# LatarTouch.net
KiCad netlist of a schematic drawn in EAGLE
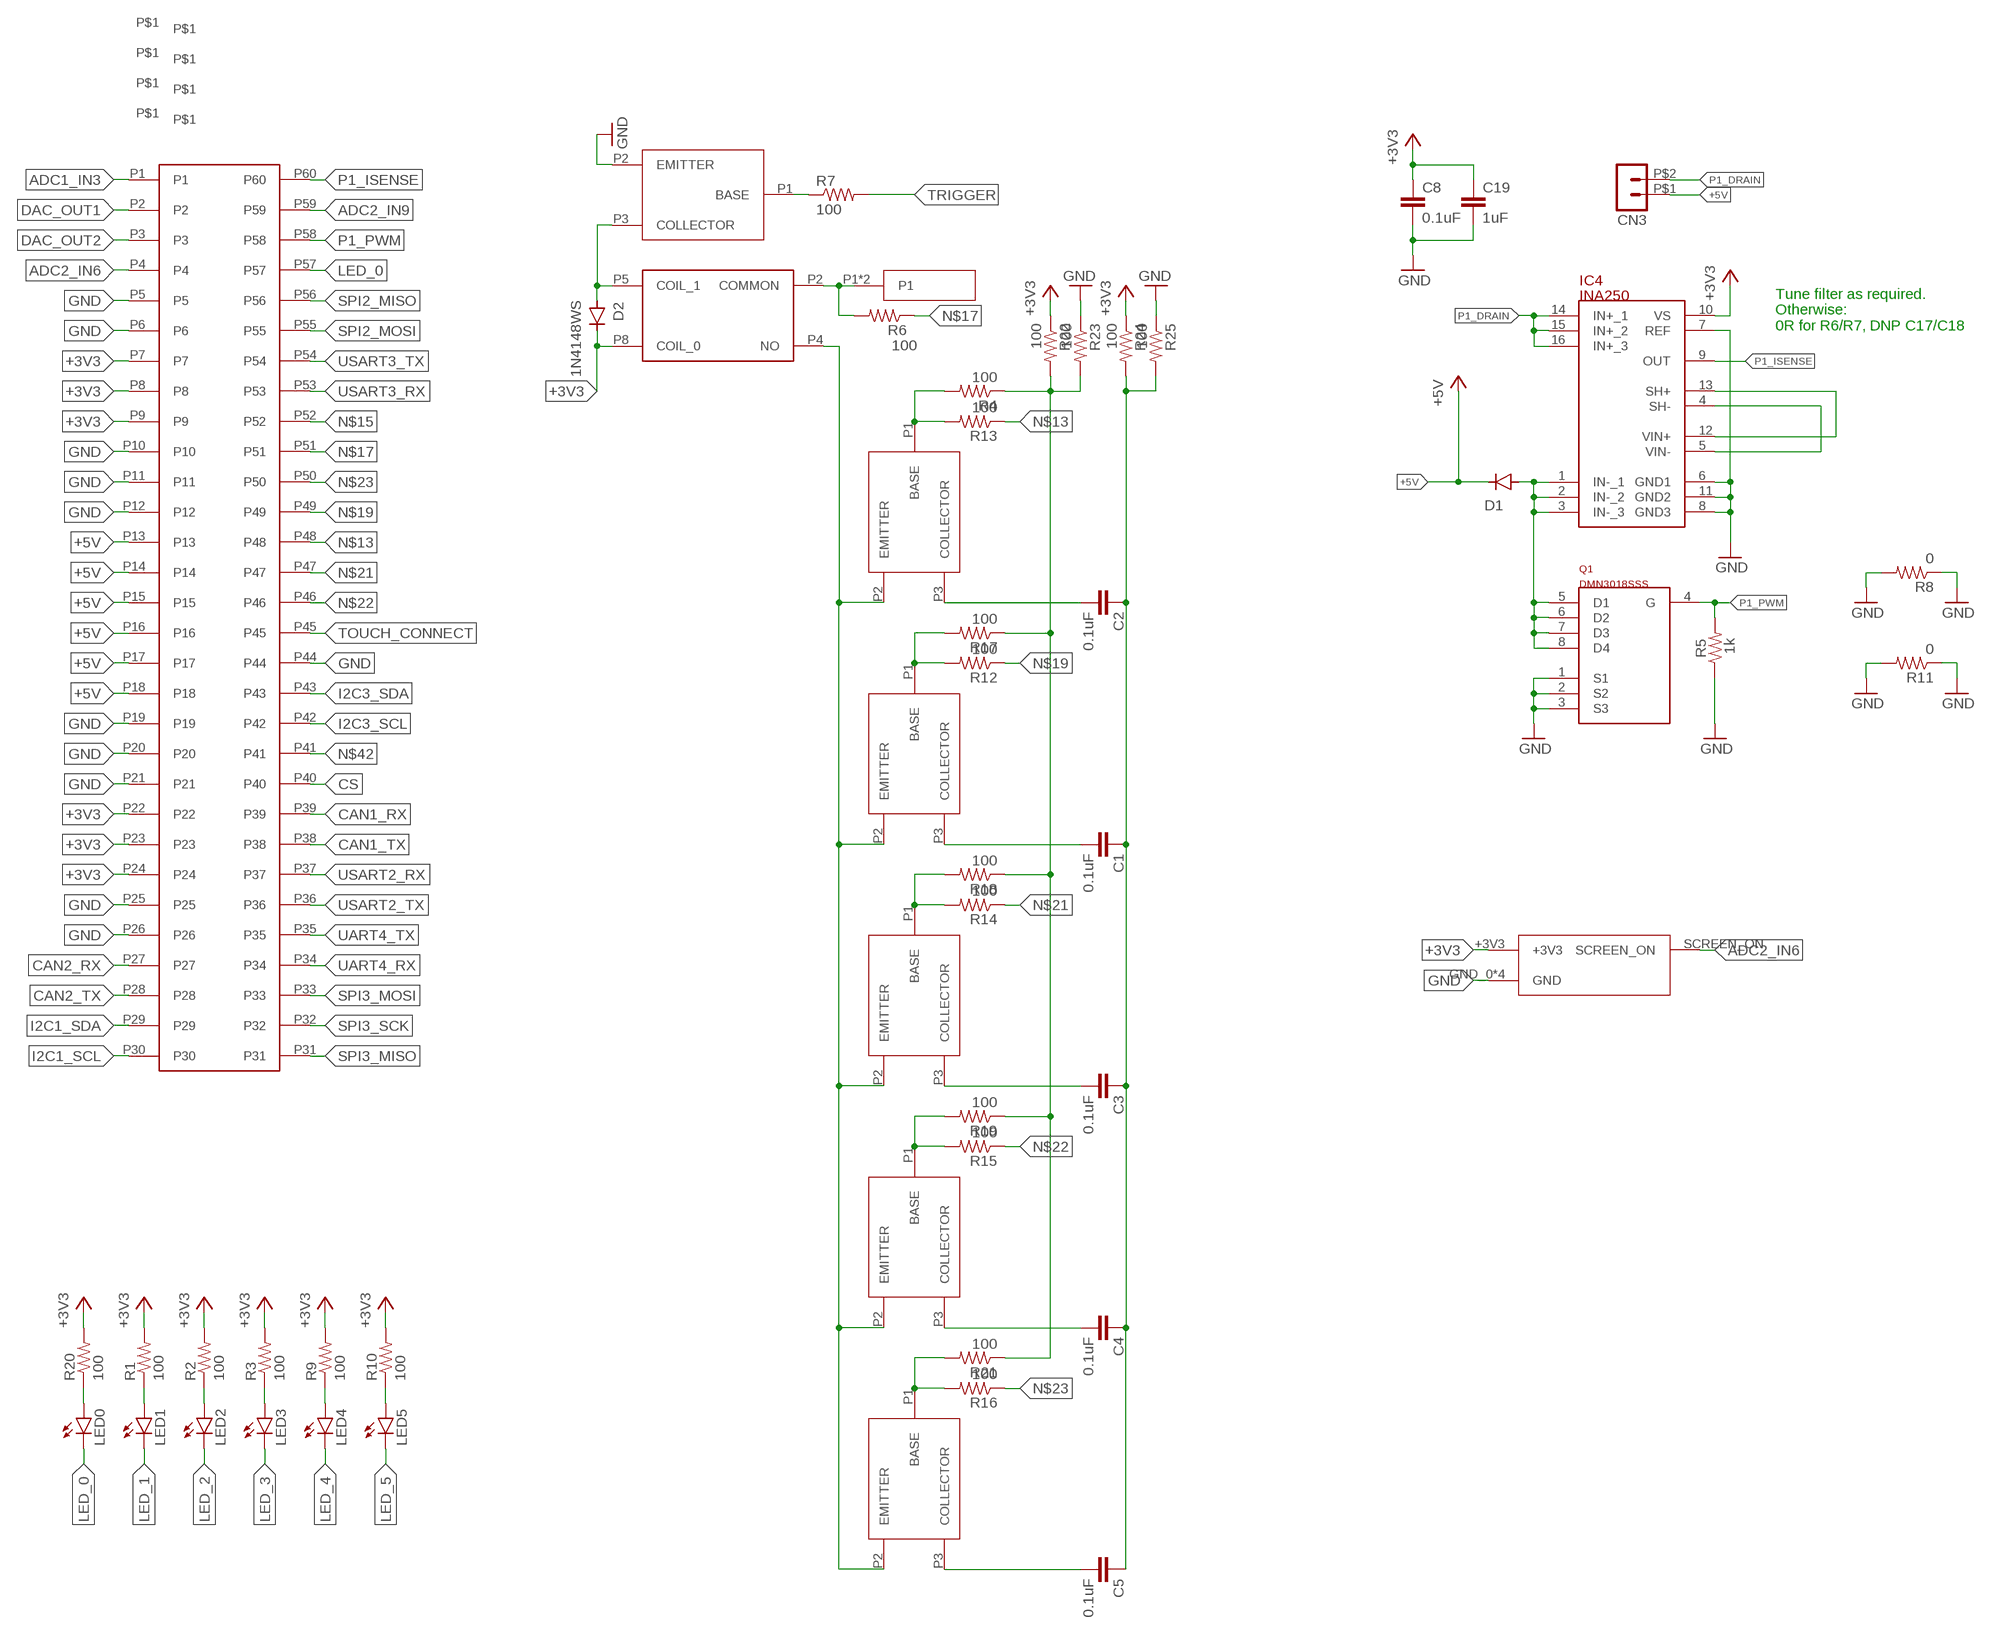
[diagram p0: schematic, sheet 1]

(export (version "E")
  (design (tool "Eeschema 10.0.6"))
  (components
    (comp (ref "C1")
      (value "0.1uF")
      (footprint "eagle-import:C0603")
      (libsource (lib "eagle-import") (part "C-EUC0603"))
    )
    (comp (ref "C2")
      (value "0.1uF")
      (footprint "eagle-import:C0603")
      (libsource (lib "eagle-import") (part "C-EUC0603"))
    )
    (comp (ref "C3")
      (value "0.1uF")
      (footprint "eagle-import:C0603")
      (libsource (lib "eagle-import") (part "C-EUC0603"))
    )
    (comp (ref "C4")
      (value "0.1uF")
      (footprint "eagle-import:C0603")
      (libsource (lib "eagle-import") (part "C-EUC0603"))
    )
    (comp (ref "C5")
      (value "0.1uF")
      (footprint "eagle-import:C0603")
      (libsource (lib "eagle-import") (part "C-EUC0603"))
    )
    (comp (ref "C8")
      (value "0.1uF")
      (footprint "eagle-import:C0805")
      (libsource (lib "eagle-import") (part "C-EUC0805"))
    )
    (comp (ref "C19")
      (value "1uF")
      (footprint "eagle-import:C0805")
      (libsource (lib "eagle-import") (part "C-EUC0805"))
    )
    (comp (ref "CN3")
      (value "HEADER_POS2_43650-0212")
      (footprint "eagle-import:43650-0212")
      (libsource (lib "eagle-import") (part "HEADER_POS2_?43650-0212"))
    )
    (comp (ref "D1")
      (value "DIODE-DO214AC")
      (footprint "eagle-import:DO214AC")
      (libsource (lib "eagle-import") (part "DIODE-DO214AC"))
    )
    (comp (ref "D2")
      (value "1N4148WS")
      (footprint "eagle-import:SOD-323")
      (fields
        (field (name "DIGIKEY_PART_NUMBER") "1N4148WSFSTR-ND")
        (field (name "MANUFACTURER") "Diodes Incorporated")
        (field (name "CREATED_BY") "PCBLayout.com")
      )
      (libsource (lib "eagle-import") (part "1N4148WS"))
    )
    (comp (ref "IC4")
      (value "INA250")
      (footprint "eagle-import:TSSOP16")
      (libsource (lib "eagle-import") (part "INA250"))
    )
    (comp (ref "LED0")
      (value "LEDCHIPLED_0603")
      (footprint "eagle-import:CHIPLED_0603")
      (libsource (lib "eagle-import") (part "LEDCHIPLED_0603"))
    )
    (comp (ref "LED1")
      (value "LEDCHIPLED_0603")
      (footprint "eagle-import:CHIPLED_0603")
      (libsource (lib "eagle-import") (part "LEDCHIPLED_0603"))
    )
    (comp (ref "LED2")
      (value "LEDCHIPLED_0603")
      (footprint "eagle-import:CHIPLED_0603")
      (libsource (lib "eagle-import") (part "LEDCHIPLED_0603"))
    )
    (comp (ref "LED3")
      (value "LEDCHIPLED_0603")
      (footprint "eagle-import:CHIPLED_0603")
      (libsource (lib "eagle-import") (part "LEDCHIPLED_0603"))
    )
    (comp (ref "LED4")
      (value "LEDCHIPLED_0603")
      (footprint "eagle-import:CHIPLED_0603")
      (libsource (lib "eagle-import") (part "LEDCHIPLED_0603"))
    )
    (comp (ref "LED5")
      (value "LEDCHIPLED_0603")
      (footprint "eagle-import:CHIPLED_0603")
      (libsource (lib "eagle-import") (part "LEDCHIPLED_0603"))
    )
    (comp (ref "Q1")
      (value "DMN3018SSS")
      (footprint "eagle-import:SO08")
      (libsource (lib "eagle-import") (part "DMN3018SSS"))
    )
    (comp (ref "R1")
      (value "100")
      (footprint "eagle-import:R0603")
      (libsource (lib "eagle-import") (part "R-US_R0603"))
    )
    (comp (ref "R2")
      (value "100")
      (footprint "eagle-import:R0603")
      (libsource (lib "eagle-import") (part "R-US_R0603"))
    )
    (comp (ref "R3")
      (value "100")
      (footprint "eagle-import:R0603")
      (libsource (lib "eagle-import") (part "R-US_R0603"))
    )
    (comp (ref "R4")
      (value "100")
      (footprint "eagle-import:R0603")
      (libsource (lib "eagle-import") (part "resistor_348_R-US_R0603"))
    )
    (comp (ref "R5")
      (value "1k")
      (footprint "eagle-import:0805")
      (libsource (lib "eagle-import") (part "RESISTOR0805"))
    )
    (comp (ref "R6")
      (value "100")
      (footprint "eagle-import:R0603")
      (libsource (lib "eagle-import") (part "R-US_R0603"))
    )
    (comp (ref "R7")
      (value "100")
      (footprint "eagle-import:R0603")
      (libsource (lib "eagle-import") (part "R-US_R0603"))
    )
    (comp (ref "R8")
      (value "0")
      (footprint "eagle-import:R0603")
      (libsource (lib "eagle-import") (part "R-US_R0603"))
    )
    (comp (ref "R9")
      (value "100")
      (footprint "eagle-import:R0603")
      (libsource (lib "eagle-import") (part "R-US_R0603"))
    )
    (comp (ref "R10")
      (value "100")
      (footprint "eagle-import:R0603")
      (libsource (lib "eagle-import") (part "R-US_R0603"))
    )
    (comp (ref "R11")
      (value "0")
      (footprint "eagle-import:R1206")
      (libsource (lib "eagle-import") (part "resistor_348_R-US_R1206"))
    )
    (comp (ref "R12")
      (value "100")
      (footprint "eagle-import:R0603")
      (libsource (lib "eagle-import") (part "resistor_348_R-US_R0603"))
    )
    (comp (ref "R13")
      (value "100")
      (footprint "eagle-import:R0603")
      (libsource (lib "eagle-import") (part "resistor_348_R-US_R0603"))
    )
    (comp (ref "R14")
      (value "100")
      (footprint "eagle-import:R0603")
      (libsource (lib "eagle-import") (part "resistor_348_R-US_R0603"))
    )
    (comp (ref "R15")
      (value "100")
      (footprint "eagle-import:R0603")
      (libsource (lib "eagle-import") (part "resistor_348_R-US_R0603"))
    )
    (comp (ref "R16")
      (value "100")
      (footprint "eagle-import:R0603")
      (libsource (lib "eagle-import") (part "resistor_348_R-US_R0603"))
    )
    (comp (ref "R17")
      (value "100")
      (footprint "eagle-import:R0603")
      (libsource (lib "eagle-import") (part "resistor_348_R-US_R0603"))
    )
    (comp (ref "R18")
      (value "100")
      (footprint "eagle-import:R0603")
      (libsource (lib "eagle-import") (part "resistor_348_R-US_R0603"))
    )
    (comp (ref "R19")
      (value "100")
      (footprint "eagle-import:R0603")
      (libsource (lib "eagle-import") (part "resistor_348_R-US_R0603"))
    )
    (comp (ref "R20")
      (value "100")
      (footprint "eagle-import:R0603")
      (libsource (lib "eagle-import") (part "R-US_R0603"))
    )
    (comp (ref "R21")
      (value "100")
      (footprint "eagle-import:R0603")
      (libsource (lib "eagle-import") (part "resistor_348_R-US_R0603"))
    )
    (comp (ref "R22")
      (value "100")
      (footprint "eagle-import:R0603")
      (libsource (lib "eagle-import") (part "resistor_348_R-US_R0603"))
    )
    (comp (ref "R23")
      (value "100")
      (footprint "eagle-import:R0603")
      (libsource (lib "eagle-import") (part "resistor_348_R-US_R0603"))
    )
    (comp (ref "R24")
      (value "100")
      (footprint "eagle-import:R0603")
      (libsource (lib "eagle-import") (part "resistor_348_R-US_R0603"))
    )
    (comp (ref "R25")
      (value "100")
      (footprint "eagle-import:R0603")
      (libsource (lib "eagle-import") (part "resistor_348_R-US_R0603"))
    )
    (comp (ref "U$4")
      (value "TOUCH")
      (footprint "eagle-import:TOUCH_PROBE")
      (libsource (lib "eagle-import") (part "TOUCH_PROBE"))
    )
    (comp (ref "U$5")
      (value "MMBT3904")
      (footprint "eagle-import:SOT23")
      (libsource (lib "eagle-import") (part "MMBT3904"))
    )
    (comp (ref "U$6")
      (value "DF12(3.0)-60DS-0.5V(86)")
      (footprint "eagle-import:DF12(3.0)-60DS-0.5V(86)")
      (libsource (lib "eagle-import") (part "DF12(3.0)-60DS-0.5V(86)"))
    )
    (comp (ref "U$7")
      (value "9774030360R")
      (footprint "eagle-import:9774030360R")
      (libsource (lib "eagle-import") (part "9774030360R"))
    )
    (comp (ref "U$8")
      (value "DETECT_DAUGHTER_BOARD")
      (footprint "eagle-import:DETECT_DAUGHTER_BOARD")
      (libsource (lib "eagle-import") (part "DETECT_DAUGHTER_BOARD"))
    )
    (comp (ref "U$9")
      (value "9774030360R")
      (footprint "eagle-import:9774030360R")
      (libsource (lib "eagle-import") (part "9774030360R"))
    )
    (comp (ref "U$10")
      (value "9774030360R")
      (footprint "eagle-import:9774030360R")
      (libsource (lib "eagle-import") (part "9774030360R"))
    )
    (comp (ref "U$11")
      (value "9774030360R")
      (footprint "eagle-import:9774030360R")
      (libsource (lib "eagle-import") (part "9774030360R"))
    )
    (comp (ref "U$14")
      (value "G6L-1F")
      (footprint "eagle-import:G6L-1F")
      (libsource (lib "eagle-import") (part "G6L-1F"))
    )
    (comp (ref "U$15")
      (value "MMBT3904")
      (footprint "eagle-import:SOT23")
      (libsource (lib "eagle-import") (part "MMBT3904"))
    )
    (comp (ref "U$16")
      (value "MMBT3904")
      (footprint "eagle-import:SOT23")
      (libsource (lib "eagle-import") (part "MMBT3904"))
    )
    (comp (ref "U$17")
      (value "MMBT3904")
      (footprint "eagle-import:SOT23")
      (libsource (lib "eagle-import") (part "MMBT3904"))
    )
    (comp (ref "U$18")
      (value "MMBT3904")
      (footprint "eagle-import:SOT23")
      (libsource (lib "eagle-import") (part "MMBT3904"))
    )
    (comp (ref "U$19")
      (value "MMBT3904")
      (footprint "eagle-import:SOT23")
      (libsource (lib "eagle-import") (part "MMBT3904"))
    )
  )
  (nets
    (net (code "1") (name "+3V3") (class "Default")
      (node (ref "C19") (pin "1") (pinfunction "1_1") (pintype "passive"))
      (node (ref "C8") (pin "1") (pinfunction "1_1") (pintype "passive"))
      (node (ref "IC4") (pin "10") (pinfunction "VS_10") (pintype "bidirectional"))
      (node (ref "R1") (pin "2") (pinfunction "2_2") (pintype "passive"))
      (node (ref "R10") (pin "2") (pinfunction "2_2") (pintype "passive"))
      (node (ref "R2") (pin "2") (pinfunction "2_2") (pintype "passive"))
      (node (ref "R20") (pin "2") (pinfunction "2_2") (pintype "passive"))
      (node (ref "R22") (pin "1") (pinfunction "1_1") (pintype "passive"))
      (node (ref "R24") (pin "1") (pinfunction "1_1") (pintype "passive"))
      (node (ref "R3") (pin "2") (pinfunction "2_2") (pintype "passive"))
      (node (ref "R9") (pin "2") (pinfunction "2_2") (pintype "passive"))
      (node (ref "U$6") (pin "P22") (pinfunction "P22_P22") (pintype "bidirectional"))
      (node (ref "U$6") (pin "P23") (pinfunction "P23_P23") (pintype "bidirectional"))
      (node (ref "U$6") (pin "P24") (pinfunction "P24_P24") (pintype "bidirectional"))
      (node (ref "U$6") (pin "P7") (pinfunction "P7_P7") (pintype "bidirectional"))
      (node (ref "U$6") (pin "P8") (pinfunction "P8_P8") (pintype "bidirectional"))
      (node (ref "U$6") (pin "P9") (pinfunction "P9_P9") (pintype "bidirectional"))
      (node (ref "U$8") (pin "+3V3") (pinfunction "+3V3_+3V3") (pintype "bidirectional"))
    )
    (net (code "2") (name "+5V") (class "Default")
      (node (ref "CN3") (pin "P$1") (pinfunction "1_P$1") (pintype "passive"))
      (node (ref "D1") (pin "C") (pinfunction "C_C") (pintype "passive"))
      (node (ref "U$6") (pin "P13") (pinfunction "P13_P13") (pintype "bidirectional"))
      (node (ref "U$6") (pin "P14") (pinfunction "P14_P14") (pintype "bidirectional"))
      (node (ref "U$6") (pin "P15") (pinfunction "P15_P15") (pintype "bidirectional"))
      (node (ref "U$6") (pin "P16") (pinfunction "P16_P16") (pintype "bidirectional"))
      (node (ref "U$6") (pin "P17") (pinfunction "P17_P17") (pintype "bidirectional"))
      (node (ref "U$6") (pin "P18") (pinfunction "P18_P18") (pintype "bidirectional"))
    )
    (net (code "3") (name "ADC1_IN3") (class "Default")
      (node (ref "U$6") (pin "P1") (pinfunction "P1_P1") (pintype "bidirectional"))
    )
    (net (code "4") (name "ADC2_IN6") (class "Default")
      (node (ref "U$6") (pin "P4") (pinfunction "P4_P4") (pintype "bidirectional"))
      (node (ref "U$8") (pin "SCREEN_ON") (pinfunction "SCREEN_ON_SCREEN_ON") (pintype "bidirectional"))
    )
    (net (code "5") (name "ADC2_IN9") (class "Default")
      (node (ref "U$6") (pin "P59") (pinfunction "P59_P59") (pintype "bidirectional"))
    )
    (net (code "6") (name "CAN1_RX") (class "Default")
      (node (ref "U$6") (pin "P39") (pinfunction "P39_P39") (pintype "bidirectional"))
    )
    (net (code "7") (name "CAN1_TX") (class "Default")
      (node (ref "U$6") (pin "P38") (pinfunction "P38_P38") (pintype "bidirectional"))
    )
    (net (code "8") (name "CAN2_RX") (class "Default")
      (node (ref "U$6") (pin "P27") (pinfunction "P27_P27") (pintype "bidirectional"))
    )
    (net (code "9") (name "CAN2_TX") (class "Default")
      (node (ref "U$6") (pin "P28") (pinfunction "P28_P28") (pintype "bidirectional"))
    )
    (net (code "10") (name "CS") (class "Default")
      (node (ref "U$6") (pin "P40") (pinfunction "P40_P40") (pintype "bidirectional"))
    )
    (net (code "11") (name "DAC_OUT1") (class "Default")
      (node (ref "U$6") (pin "P2") (pinfunction "P2_P2") (pintype "bidirectional"))
    )
    (net (code "12") (name "DAC_OUT2") (class "Default")
      (node (ref "U$6") (pin "P3") (pinfunction "P3_P3") (pintype "bidirectional"))
    )
    (net (code "13") (name "GND") (class "Default")
      (node (ref "C19") (pin "2") (pinfunction "2_2") (pintype "passive"))
      (node (ref "C8") (pin "2") (pinfunction "2_2") (pintype "passive"))
      (node (ref "IC4") (pin "11") (pinfunction "GND2_11") (pintype "bidirectional"))
      (node (ref "IC4") (pin "6") (pinfunction "GND1_6") (pintype "bidirectional"))
      (node (ref "IC4") (pin "7") (pinfunction "REF_7") (pintype "bidirectional"))
      (node (ref "IC4") (pin "8") (pinfunction "GND3_8") (pintype "bidirectional"))
      (node (ref "Q1") (pin "1") (pinfunction "S1_1") (pintype "bidirectional"))
      (node (ref "Q1") (pin "2") (pinfunction "S2_2") (pintype "bidirectional"))
      (node (ref "Q1") (pin "3") (pinfunction "S3_3") (pintype "bidirectional"))
      (node (ref "R11") (pin "1") (pinfunction "1_1") (pintype "passive"))
      (node (ref "R11") (pin "2") (pinfunction "2_2") (pintype "passive"))
      (node (ref "R23") (pin "1") (pinfunction "1_1") (pintype "passive"))
      (node (ref "R25") (pin "1") (pinfunction "1_1") (pintype "passive"))
      (node (ref "R5") (pin "1") (pinfunction "1_1") (pintype "passive"))
      (node (ref "R8") (pin "1") (pinfunction "1_1") (pintype "passive"))
      (node (ref "R8") (pin "2") (pinfunction "2_2") (pintype "passive"))
      (node (ref "U$15") (pin "P2") (pinfunction "EMITTER_P2") (pintype "bidirectional"))
      (node (ref "U$6") (pin "P10") (pinfunction "P10_P10") (pintype "bidirectional"))
      (node (ref "U$6") (pin "P11") (pinfunction "P11_P11") (pintype "bidirectional"))
      (node (ref "U$6") (pin "P12") (pinfunction "P12_P12") (pintype "bidirectional"))
      (node (ref "U$6") (pin "P19") (pinfunction "P19_P19") (pintype "bidirectional"))
      (node (ref "U$6") (pin "P20") (pinfunction "P20_P20") (pintype "bidirectional"))
      (node (ref "U$6") (pin "P21") (pinfunction "P21_P21") (pintype "bidirectional"))
      (node (ref "U$6") (pin "P25") (pinfunction "P25_P25") (pintype "bidirectional"))
      (node (ref "U$6") (pin "P26") (pinfunction "P26_P26") (pintype "bidirectional"))
      (node (ref "U$6") (pin "P44") (pinfunction "P44_P44") (pintype "bidirectional"))
      (node (ref "U$6") (pin "P5") (pinfunction "P5_P5") (pintype "bidirectional"))
      (node (ref "U$6") (pin "P6") (pinfunction "P6_P6") (pintype "bidirectional"))
      (node (ref "U$8") (pin "GND_0") (pinfunction "GND_GND_0") (pintype "bidirectional"))
      (node (ref "U$8") (pin "GND_1") (pinfunction "GND_GND_1") (pintype "bidirectional"))
      (node (ref "U$8") (pin "GND_2") (pinfunction "GND_GND_2") (pintype "bidirectional"))
      (node (ref "U$8") (pin "GND_3") (pinfunction "GND_GND_3") (pintype "bidirectional"))
    )
    (net (code "14") (name "I2C1_SCL") (class "Default")
      (node (ref "U$6") (pin "P30") (pinfunction "P30_P30") (pintype "bidirectional"))
    )
    (net (code "15") (name "I2C1_SDA") (class "Default")
      (node (ref "U$6") (pin "P29") (pinfunction "P29_P29") (pintype "bidirectional"))
    )
    (net (code "16") (name "I2C3_SCL") (class "Default")
      (node (ref "U$6") (pin "P42") (pinfunction "P42_P42") (pintype "bidirectional"))
    )
    (net (code "17") (name "I2C3_SDA") (class "Default")
      (node (ref "U$6") (pin "P43") (pinfunction "P43_P43") (pintype "bidirectional"))
    )
    (net (code "18") (name "LED_0") (class "Default")
      (node (ref "LED0") (pin "C") (pinfunction "C_C") (pintype "passive"))
      (node (ref "U$6") (pin "P57") (pinfunction "P57_P57") (pintype "bidirectional"))
    )
    (net (code "19") (name "LED_1") (class "Default")
      (node (ref "LED1") (pin "C") (pinfunction "C_C") (pintype "passive"))
    )
    (net (code "20") (name "LED_2") (class "Default")
      (node (ref "LED2") (pin "C") (pinfunction "C_C") (pintype "passive"))
    )
    (net (code "21") (name "LED_3") (class "Default")
      (node (ref "LED3") (pin "C") (pinfunction "C_C") (pintype "passive"))
    )
    (net (code "22") (name "LED_4") (class "Default")
      (node (ref "LED4") (pin "C") (pinfunction "C_C") (pintype "passive"))
    )
    (net (code "23") (name "LED_5") (class "Default")
      (node (ref "LED5") (pin "C") (pinfunction "C_C") (pintype "passive"))
    )
    (net (code "24") (name "N$13") (class "Default")
      (node (ref "R13") (pin "1") (pinfunction "1_1") (pintype "passive"))
      (node (ref "U$6") (pin "P48") (pinfunction "P48_P48") (pintype "bidirectional"))
    )
    (net (code "25") (name "N$15") (class "Default")
      (node (ref "U$6") (pin "P52") (pinfunction "P52_P52") (pintype "bidirectional"))
    )
    (net (code "26") (name "N$17") (class "Default")
      (node (ref "R6") (pin "1") (pinfunction "1_1") (pintype "passive"))
      (node (ref "U$6") (pin "P51") (pinfunction "P51_P51") (pintype "bidirectional"))
    )
    (net (code "27") (name "N$19") (class "Default")
      (node (ref "R12") (pin "1") (pinfunction "1_1") (pintype "passive"))
      (node (ref "U$6") (pin "P49") (pinfunction "P49_P49") (pintype "bidirectional"))
    )
    (net (code "28") (name "N$21") (class "Default")
      (node (ref "R14") (pin "1") (pinfunction "1_1") (pintype "passive"))
      (node (ref "U$6") (pin "P47") (pinfunction "P47_P47") (pintype "bidirectional"))
    )
    (net (code "29") (name "N$22") (class "Default")
      (node (ref "R15") (pin "1") (pinfunction "1_1") (pintype "passive"))
      (node (ref "U$6") (pin "P46") (pinfunction "P46_P46") (pintype "bidirectional"))
    )
    (net (code "30") (name "N$23") (class "Default")
      (node (ref "R16") (pin "1") (pinfunction "1_1") (pintype "passive"))
      (node (ref "U$6") (pin "P50") (pinfunction "P50_P50") (pintype "bidirectional"))
    )
    (net (code "31") (name "N$42") (class "Default")
      (node (ref "U$6") (pin "P41") (pinfunction "P41_P41") (pintype "bidirectional"))
    )
    (net (code "32") (name "Net-(C1-Pad1)") (class "Default")
      (node (ref "C1") (pin "1") (pinfunction "1_1") (pintype "passive"))
      (node (ref "C2") (pin "1") (pinfunction "1_1") (pintype "passive"))
      (node (ref "C3") (pin "1") (pinfunction "1_1") (pintype "passive"))
      (node (ref "C4") (pin "1") (pinfunction "1_1") (pintype "passive"))
      (node (ref "C5") (pin "1") (pinfunction "1_1") (pintype "passive"))
      (node (ref "R24") (pin "2") (pinfunction "2_2") (pintype "passive"))
      (node (ref "R25") (pin "2") (pinfunction "2_2") (pintype "passive"))
    )
    (net (code "33") (name "Net-(IC4-IN-_1)") (class "Default")
      (node (ref "D1") (pin "A") (pinfunction "A_A") (pintype "passive"))
      (node (ref "IC4") (pin "1") (pinfunction "IN-_1_1") (pintype "bidirectional"))
      (node (ref "IC4") (pin "2") (pinfunction "IN-_2_2") (pintype "bidirectional"))
      (node (ref "IC4") (pin "3") (pinfunction "IN-_3_3") (pintype "bidirectional"))
      (node (ref "Q1") (pin "5") (pinfunction "D1_5") (pintype "bidirectional"))
      (node (ref "Q1") (pin "6") (pinfunction "D2_6") (pintype "bidirectional"))
      (node (ref "Q1") (pin "7") (pinfunction "D3_7") (pintype "bidirectional"))
      (node (ref "Q1") (pin "8") (pinfunction "D4_8") (pintype "bidirectional"))
    )
    (net (code "34") (name "Net-(IC4-SH+)") (class "Default")
      (node (ref "IC4") (pin "12") (pinfunction "VIN+_12") (pintype "bidirectional"))
      (node (ref "IC4") (pin "13") (pinfunction "SH+_13") (pintype "bidirectional"))
    )
    (net (code "35") (name "Net-(IC4-SH-)") (class "Default")
      (node (ref "IC4") (pin "4") (pinfunction "SH-_4") (pintype "bidirectional"))
      (node (ref "IC4") (pin "5") (pinfunction "VIN-_5") (pintype "bidirectional"))
    )
    (net (code "36") (name "Net-(LED0-PadA)") (class "Default")
      (node (ref "LED0") (pin "A") (pinfunction "A_A") (pintype "passive"))
      (node (ref "R20") (pin "1") (pinfunction "1_1") (pintype "passive"))
    )
    (net (code "37") (name "Net-(LED1-PadA)") (class "Default")
      (node (ref "LED1") (pin "A") (pinfunction "A_A") (pintype "passive"))
      (node (ref "R1") (pin "1") (pinfunction "1_1") (pintype "passive"))
    )
    (net (code "38") (name "Net-(LED2-PadA)") (class "Default")
      (node (ref "LED2") (pin "A") (pinfunction "A_A") (pintype "passive"))
      (node (ref "R2") (pin "1") (pinfunction "1_1") (pintype "passive"))
    )
    (net (code "39") (name "Net-(LED3-PadA)") (class "Default")
      (node (ref "LED3") (pin "A") (pinfunction "A_A") (pintype "passive"))
      (node (ref "R3") (pin "1") (pinfunction "1_1") (pintype "passive"))
    )
    (net (code "40") (name "Net-(LED4-PadA)") (class "Default")
      (node (ref "LED4") (pin "A") (pinfunction "A_A") (pintype "passive"))
      (node (ref "R9") (pin "1") (pinfunction "1_1") (pintype "passive"))
    )
    (net (code "41") (name "Net-(LED5-PadA)") (class "Default")
      (node (ref "LED5") (pin "A") (pinfunction "A_A") (pintype "passive"))
      (node (ref "R10") (pin "1") (pinfunction "1_1") (pintype "passive"))
    )
    (net (code "42") (name "Net-(R17-Pad1)") (class "Default")
      (node (ref "R17") (pin "1") (pinfunction "1_1") (pintype "passive"))
      (node (ref "R18") (pin "1") (pinfunction "1_1") (pintype "passive"))
      (node (ref "R19") (pin "1") (pinfunction "1_1") (pintype "passive"))
      (node (ref "R21") (pin "1") (pinfunction "1_1") (pintype "passive"))
      (node (ref "R22") (pin "2") (pinfunction "2_2") (pintype "passive"))
      (node (ref "R23") (pin "2") (pinfunction "2_2") (pintype "passive"))
      (node (ref "R4") (pin "1") (pinfunction "1_1") (pintype "passive"))
    )
    (net (code "43") (name "Net-(U$5-BASE)") (class "Default")
      (node (ref "R13") (pin "2") (pinfunction "2_2") (pintype "passive"))
      (node (ref "R4") (pin "2") (pinfunction "2_2") (pintype "passive"))
      (node (ref "U$5") (pin "P1") (pinfunction "BASE_P1") (pintype "bidirectional"))
    )
    (net (code "44") (name "Net-(U$5-COLLECTOR)") (class "Default")
      (node (ref "C2") (pin "2") (pinfunction "2_2") (pintype "passive"))
      (node (ref "U$5") (pin "P3") (pinfunction "COLLECTOR_P3") (pintype "bidirectional"))
    )
    (net (code "45") (name "Net-(U$14-COIL_0)") (class "Default")
      (node (ref "D2") (pin "C") (pinfunction "C_C") (pintype "passive"))
      (node (ref "U$14") (pin "P8") (pinfunction "COIL_0_P8") (pintype "bidirectional"))
    )
    (net (code "46") (name "Net-(U$14-COIL_1)") (class "Default")
      (node (ref "D2") (pin "A") (pinfunction "A_A") (pintype "passive"))
      (node (ref "U$14") (pin "P5") (pinfunction "COIL_1_P5") (pintype "bidirectional"))
      (node (ref "U$15") (pin "P3") (pinfunction "COLLECTOR_P3") (pintype "bidirectional"))
    )
    (net (code "47") (name "Net-(U$14-COMMON)") (class "Default")
      (node (ref "R6") (pin "2") (pinfunction "2_2") (pintype "passive"))
      (node (ref "U$14") (pin "P2") (pinfunction "COMMON_P2") (pintype "bidirectional"))
      (node (ref "U$4") (pin "P1") (pinfunction "P1_P1") (pintype "bidirectional"))
      (node (ref "U$4") (pin "P2") (pinfunction "P1_P2") (pintype "bidirectional"))
    )
    (net (code "48") (name "Net-(U$14-NO)") (class "Default")
      (node (ref "U$14") (pin "P4") (pinfunction "NO_P4") (pintype "bidirectional"))
      (node (ref "U$16") (pin "P2") (pinfunction "EMITTER_P2") (pintype "bidirectional"))
      (node (ref "U$17") (pin "P2") (pinfunction "EMITTER_P2") (pintype "bidirectional"))
      (node (ref "U$18") (pin "P2") (pinfunction "EMITTER_P2") (pintype "bidirectional"))
      (node (ref "U$19") (pin "P2") (pinfunction "EMITTER_P2") (pintype "bidirectional"))
      (node (ref "U$5") (pin "P2") (pinfunction "EMITTER_P2") (pintype "bidirectional"))
    )
    (net (code "49") (name "Net-(U$15-BASE)") (class "Default")
      (node (ref "R7") (pin "1") (pinfunction "1_1") (pintype "passive"))
      (node (ref "U$15") (pin "P1") (pinfunction "BASE_P1") (pintype "bidirectional"))
    )
    (net (code "50") (name "Net-(U$16-BASE)") (class "Default")
      (node (ref "R12") (pin "2") (pinfunction "2_2") (pintype "passive"))
      (node (ref "R17") (pin "2") (pinfunction "2_2") (pintype "passive"))
      (node (ref "U$16") (pin "P1") (pinfunction "BASE_P1") (pintype "bidirectional"))
    )
    (net (code "51") (name "Net-(U$16-COLLECTOR)") (class "Default")
      (node (ref "C1") (pin "2") (pinfunction "2_2") (pintype "passive"))
      (node (ref "U$16") (pin "P3") (pinfunction "COLLECTOR_P3") (pintype "bidirectional"))
    )
    (net (code "52") (name "Net-(U$17-BASE)") (class "Default")
      (node (ref "R14") (pin "2") (pinfunction "2_2") (pintype "passive"))
      (node (ref "R18") (pin "2") (pinfunction "2_2") (pintype "passive"))
      (node (ref "U$17") (pin "P1") (pinfunction "BASE_P1") (pintype "bidirectional"))
    )
    (net (code "53") (name "Net-(U$17-COLLECTOR)") (class "Default")
      (node (ref "C3") (pin "2") (pinfunction "2_2") (pintype "passive"))
      (node (ref "U$17") (pin "P3") (pinfunction "COLLECTOR_P3") (pintype "bidirectional"))
    )
    (net (code "54") (name "Net-(U$18-BASE)") (class "Default")
      (node (ref "R15") (pin "2") (pinfunction "2_2") (pintype "passive"))
      (node (ref "R19") (pin "2") (pinfunction "2_2") (pintype "passive"))
      (node (ref "U$18") (pin "P1") (pinfunction "BASE_P1") (pintype "bidirectional"))
    )
    (net (code "55") (name "Net-(U$18-COLLECTOR)") (class "Default")
      (node (ref "C4") (pin "2") (pinfunction "2_2") (pintype "passive"))
      (node (ref "U$18") (pin "P3") (pinfunction "COLLECTOR_P3") (pintype "bidirectional"))
    )
    (net (code "56") (name "Net-(U$19-BASE)") (class "Default")
      (node (ref "R16") (pin "2") (pinfunction "2_2") (pintype "passive"))
      (node (ref "R21") (pin "2") (pinfunction "2_2") (pintype "passive"))
      (node (ref "U$19") (pin "P1") (pinfunction "BASE_P1") (pintype "bidirectional"))
    )
    (net (code "57") (name "Net-(U$19-COLLECTOR)") (class "Default")
      (node (ref "C5") (pin "2") (pinfunction "2_2") (pintype "passive"))
      (node (ref "U$19") (pin "P3") (pinfunction "COLLECTOR_P3") (pintype "bidirectional"))
    )
    (net (code "58") (name "P1_DRAIN") (class "Default")
      (node (ref "CN3") (pin "P$2") (pinfunction "2_P$2") (pintype "passive"))
      (node (ref "IC4") (pin "14") (pinfunction "IN+_1_14") (pintype "bidirectional"))
      (node (ref "IC4") (pin "15") (pinfunction "IN+_2_15") (pintype "bidirectional"))
      (node (ref "IC4") (pin "16") (pinfunction "IN+_3_16") (pintype "bidirectional"))
    )
    (net (code "59") (name "P1_ISENSE") (class "Default")
      (node (ref "IC4") (pin "9") (pinfunction "OUT_9") (pintype "bidirectional"))
      (node (ref "U$6") (pin "P60") (pinfunction "P60_P60") (pintype "bidirectional"))
    )
    (net (code "60") (name "P1_PWM") (class "Default")
      (node (ref "Q1") (pin "4") (pinfunction "G_4") (pintype "bidirectional"))
      (node (ref "R5") (pin "2") (pinfunction "2_2") (pintype "passive"))
      (node (ref "U$6") (pin "P58") (pinfunction "P58_P58") (pintype "bidirectional"))
    )
    (net (code "61") (name "SPI2_MISO") (class "Default")
      (node (ref "U$6") (pin "P56") (pinfunction "P56_P56") (pintype "bidirectional"))
    )
    (net (code "62") (name "SPI2_MOSI") (class "Default")
      (node (ref "U$6") (pin "P55") (pinfunction "P55_P55") (pintype "bidirectional"))
    )
    (net (code "63") (name "SPI3_MISO") (class "Default")
      (node (ref "U$6") (pin "P31") (pinfunction "P31_P31") (pintype "bidirectional"))
    )
    (net (code "64") (name "SPI3_MOSI") (class "Default")
      (node (ref "U$6") (pin "P33") (pinfunction "P33_P33") (pintype "bidirectional"))
    )
    (net (code "65") (name "SPI3_SCK") (class "Default")
      (node (ref "U$6") (pin "P32") (pinfunction "P32_P32") (pintype "bidirectional"))
    )
    (net (code "66") (name "TOUCH_CONNECT") (class "Default")
      (node (ref "U$6") (pin "P45") (pinfunction "P45_P45") (pintype "bidirectional"))
    )
    (net (code "67") (name "TRIGGER") (class "Default")
      (node (ref "R7") (pin "2") (pinfunction "2_2") (pintype "passive"))
    )
    (net (code "68") (name "UART4_RX") (class "Default")
      (node (ref "U$6") (pin "P34") (pinfunction "P34_P34") (pintype "bidirectional"))
    )
    (net (code "69") (name "UART4_TX") (class "Default")
      (node (ref "U$6") (pin "P35") (pinfunction "P35_P35") (pintype "bidirectional"))
    )
    (net (code "70") (name "USART2_RX") (class "Default")
      (node (ref "U$6") (pin "P37") (pinfunction "P37_P37") (pintype "bidirectional"))
    )
    (net (code "71") (name "USART2_TX") (class "Default")
      (node (ref "U$6") (pin "P36") (pinfunction "P36_P36") (pintype "bidirectional"))
    )
    (net (code "72") (name "USART3_RX") (class "Default")
      (node (ref "U$6") (pin "P53") (pinfunction "P53_P53") (pintype "bidirectional"))
    )
    (net (code "73") (name "USART3_TX") (class "Default")
      (node (ref "U$6") (pin "P54") (pinfunction "P54_P54") (pintype "bidirectional"))
    )
    (net (code "74") (name "unconnected-(U$7-PadP$1)") (class "Default")
      (node (ref "U$7") (pin "P$1") (pinfunction "P$1_P$1") (pintype "bidirectional"))
    )
    (net (code "75") (name "unconnected-(U$9-PadP$1)") (class "Default")
      (node (ref "U$9") (pin "P$1") (pinfunction "P$1_P$1") (pintype "bidirectional"))
    )
    (net (code "76") (name "unconnected-(U$10-PadP$1)") (class "Default")
      (node (ref "U$10") (pin "P$1") (pinfunction "P$1_P$1") (pintype "bidirectional"))
    )
    (net (code "77") (name "unconnected-(U$11-PadP$1)") (class "Default")
      (node (ref "U$11") (pin "P$1") (pinfunction "P$1_P$1") (pintype "bidirectional"))
    )
  )
)
